# air_quality_monitor.net
KiCad netlist of a schematic drawn in Altium Designer
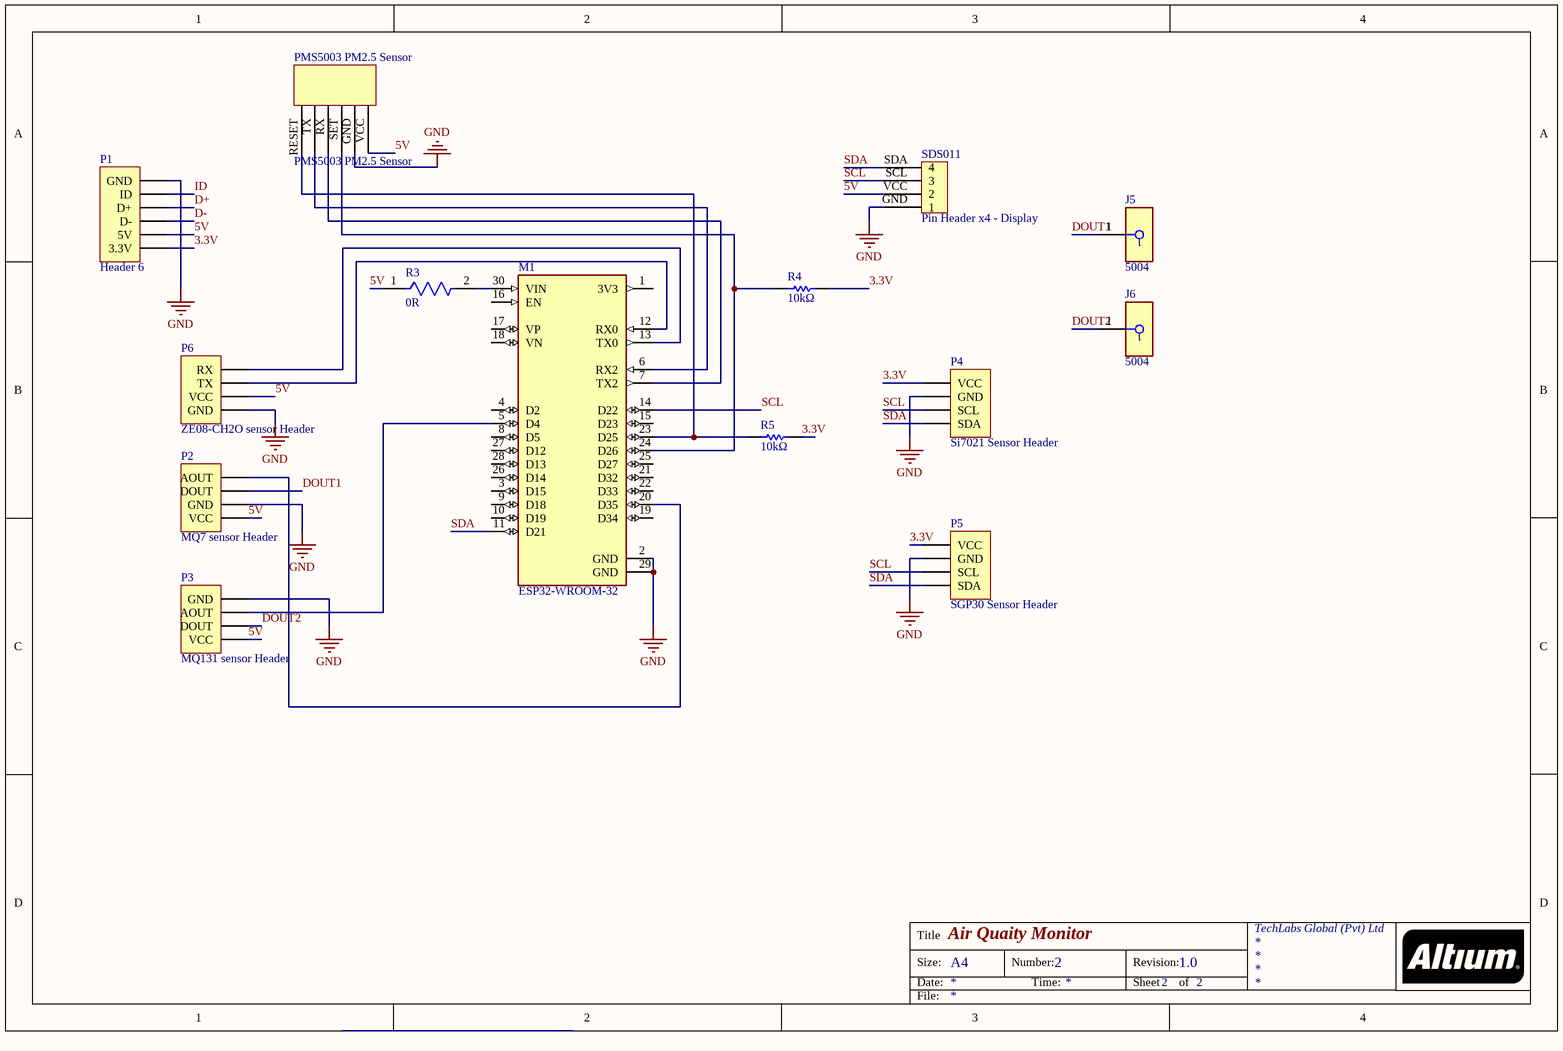
[diagram p0: air quality monitor.SchDoc]

(export (version "E")
  (design (tool "Eeschema 10.0.6"))
  (components
    (comp (ref "J5")
      (value "5004")
      (footprint "FP-5004-MFG")
      (description "PC TEST POINT MINIATURE YELLOW")
      (fields (field (name "MANUFACTURER") "Keystone") (field (name "LCSC PART #") "C2906762"))
      (libsource (lib "Altium Content Vault") (part "98815daf2f2c152b0c43f5ab9800df6"))
    )
    (comp (ref "J6")
      (value "5004")
      (footprint "FP-5004-MFG")
      (description "PC TEST POINT MINIATURE YELLOW")
      (fields (field (name "MANUFACTURER") "Keystone") (field (name "LCSC PART #") "C2906762"))
      (libsource (lib "Altium Content Vault") (part "98815daf2f2c152b0c43f5ab9800df6"))
    )
    (comp (ref "M1")
      (value "ESP32-WROOM-32")
      (footprint "ESP32-DEVKIT-V1")
      (libsource (lib "Modules") (part "ESP32-DEVKIT-V1"))
    )
    (comp (ref "P1")
      (value "Header 6")
      (footprint "HDR1X6")
      (description "Header, 6-Pin")
      (fields (field (name "PUBLISHER") "Altium Limited"))
      (libsource (lib "Miscellaneous Connectors") (part "Header 6"))
    )
    (comp (ref "P2")
      (value "MQ7 sensor Header")
      (footprint "HDR1X4")
      (description "Header, 4-Pin")
      (fields (field (name "PUBLISHER") "Altium Limited"))
      (libsource (lib "") (part "Header 4_2"))
    )
    (comp (ref "P3")
      (value "MQ131 sensor Header")
      (footprint "HDR1X4")
      (description "Header, 4-Pin")
      (fields (field (name "PUBLISHER") "Altium Limited"))
      (libsource (lib "") (part "Header 4_3"))
    )
    (comp (ref "P4")
      (value "Si7021 Sensor Header")
      (footprint "HDR1X4")
      (description "Header, 4-Pin")
      (fields (field (name "PUBLISHER") "Altium Limited"))
      (libsource (lib "") (part "Header 4_1"))
    )
    (comp (ref "P5")
      (value "SGP30 Sensor Header")
      (footprint "HDR1X4")
      (description "Header, 4-Pin")
      (fields (field (name "PUBLISHER") "Altium Limited"))
      (libsource (lib "") (part "Header 4_1"))
    )
    (comp (ref "P6")
      (value "ZE08-CH2O sensor Header")
      (footprint "HDR1X4")
      (description "Header, 4-Pin")
      (fields (field (name "PUBLISHER") "Altium Limited"))
      (libsource (lib "Miscellaneous Connectors") (part "Header 4"))
    )
    (comp (ref "PMS5003 PM2.5 Sensor")
      (value "PMS5003 PM2.5 Sensor")
      (footprint "PMS5003 PM2.5 Sensor")
      (libsource (lib "DIY Air Quality Monitor Library") (part "PMS5003 PM2.5 Sensor"))
    )
    (comp (ref "R3")
      (value "0R")
      (footprint "FP-RC0402-0_4-IPC_A")
      (description "RES SMD 0 OHM JUMPER 1/16W 0402")
      (fields (field (name "MANUFACTURER") "Yageo") (field (name "LCSC PART #") "C106231"))
      (libsource (lib "Altium Content Vault") (part "1029c3af85768c4190bb7ad29bc67b5"))
    )
    (comp (ref "R4")
      (value "10kΩ")
      (footprint "RESC1005X40X25LL05T10")
      (description "62.5mW 50V ±100ppm/℃ ±1% -55℃~+155℃ 10kΩ 0402 Chip Resistor - Surface Mount ROHS")
      (fields (field (name "MFR. PART #") "RC0402FR-0710KL") (field (name "MANUFACTURER") "Yageo / Phycomp"))
      (libsource (lib "Altium Content Vault") (part "RES"))
    )
    (comp (ref "R5")
      (value "10kΩ")
      (footprint "RESC1005X40X25LL05T10")
      (description "62.5mW 50V ±100ppm/℃ ±1% -55℃~+155℃ 10kΩ 0402 Chip Resistor - Surface Mount ROHS")
      (fields (field (name "MFR. PART #") "RC0402FR-0710KL") (field (name "MANUFACTURER") "Yageo / Phycomp"))
      (libsource (lib "Altium Content Vault") (part "RES"))
    )
    (comp (ref "SDS011")
      (value "Pin Header x4 - Display")
      (footprint "dispay")
      (libsource (lib "display") (part "Pin Header x4 - Display"))
    )
  )
  (nets
    (net (code "1") (name "/3.3V") (class "Default")
      (node (ref "P1") (pin "1") (pinfunction "3.3V_1") (pintype "passive"))
      (node (ref "P4") (pin "1") (pinfunction "VCC_1") (pintype "passive"))
      (node (ref "P5") (pin "1") (pinfunction "VCC_1") (pintype "passive"))
      (node (ref "R4") (pin "2") (pinfunction "2_2") (pintype "passive"))
      (node (ref "R5") (pin "2") (pinfunction "2_2") (pintype "passive"))
    )
    (net (code "2") (name "/5V") (class "Default")
      (node (ref "P1") (pin "2") (pinfunction "5V_2") (pintype "passive"))
      (node (ref "P2") (pin "1") (pinfunction "VCC_1") (pintype "passive"))
      (node (ref "P3") (pin "1") (pinfunction "VCC_1") (pintype "passive"))
      (node (ref "P6") (pin "2") (pinfunction "VCC_2") (pintype "passive"))
      (node (ref "PMS5003 PM2.5 Sensor") (pin "VCC") (pintype "passive"))
      (node (ref "R3") (pin "1") (pinfunction "1_1") (pintype "passive"))
      (node (ref "SDS011") (pin "VCC") (pinfunction "2_VCC") (pintype "passive"))
    )
    (net (code "3") (name "/D+") (class "Default")
      (node (ref "P1") (pin "4") (pinfunction "D+_4") (pintype "passive"))
    )
    (net (code "4") (name "/D-") (class "Default")
      (node (ref "P1") (pin "3") (pinfunction "D-_3") (pintype "passive"))
    )
    (net (code "5") (name "/DOUT1") (class "Default")
      (node (ref "J5") (pin "1") (pinfunction "1_1") (pintype "passive"))
      (node (ref "P2") (pin "3") (pinfunction "DOUT_3") (pintype "passive"))
    )
    (net (code "6") (name "/DOUT2") (class "Default")
      (node (ref "J6") (pin "1") (pinfunction "1_1") (pintype "passive"))
      (node (ref "P3") (pin "2") (pinfunction "DOUT_2") (pintype "passive"))
    )
    (net (code "7") (name "/ID") (class "Default")
      (node (ref "P1") (pin "5") (pinfunction "ID_5") (pintype "passive"))
    )
    (net (code "8") (name "/SCL") (class "Default")
      (node (ref "M1") (pin "14") (pinfunction "D22_14") (pintype "bidirectional"))
      (node (ref "P4") (pin "3") (pinfunction "SCL_3") (pintype "passive"))
      (node (ref "P5") (pin "3") (pinfunction "SCL_3") (pintype "passive"))
      (node (ref "SDS011") (pin "SCL") (pinfunction "3_SCL") (pintype "passive"))
    )
    (net (code "9") (name "/SDA") (class "Default")
      (node (ref "M1") (pin "11") (pinfunction "D21_11") (pintype "bidirectional"))
      (node (ref "P4") (pin "4") (pinfunction "SDA_4") (pintype "passive"))
      (node (ref "P5") (pin "4") (pinfunction "SDA_4") (pintype "passive"))
      (node (ref "SDS011") (pin "SDA") (pinfunction "4_SDA") (pintype "passive"))
    )
    (net (code "10") (name "GND") (class "Default")
      (node (ref "M1") (pin "2") (pinfunction "GND_2") (pintype "power_in"))
      (node (ref "M1") (pin "29") (pinfunction "GND_29") (pintype "power_in"))
      (node (ref "P1") (pin "6") (pinfunction "GND_6") (pintype "passive"))
      (node (ref "P2") (pin "2") (pinfunction "GND_2") (pintype "passive"))
      (node (ref "P3") (pin "4") (pinfunction "GND_4") (pintype "passive"))
      (node (ref "P4") (pin "2") (pinfunction "GND_2") (pintype "passive"))
      (node (ref "P5") (pin "2") (pinfunction "GND_2") (pintype "passive"))
      (node (ref "P6") (pin "1") (pinfunction "GND_1") (pintype "passive"))
      (node (ref "PMS5003 PM2.5 Sensor") (pin "GND") (pintype "passive"))
      (node (ref "SDS011") (pin "GND") (pinfunction "1_GND") (pintype "passive"))
    )
    (net (code "11") (name "Net-(M1-D4)") (class "Default")
      (node (ref "M1") (pin "5") (pinfunction "D4_5") (pintype "bidirectional"))
      (node (ref "P3") (pin "3") (pinfunction "AOUT_3") (pintype "passive"))
    )
    (net (code "12") (name "Net-(M1-D25)") (class "Default")
      (node (ref "M1") (pin "23") (pinfunction "D25_23") (pintype "bidirectional"))
      (node (ref "PMS5003 PM2.5 Sensor") (pin "RESET") (pintype "passive"))
      (node (ref "R5") (pin "1") (pinfunction "1_1") (pintype "passive"))
    )
    (net (code "13") (name "Net-(M1-D26)") (class "Default")
      (node (ref "M1") (pin "24") (pinfunction "D26_24") (pintype "bidirectional"))
      (node (ref "PMS5003 PM2.5 Sensor") (pin "SET") (pintype "passive"))
      (node (ref "R4") (pin "1") (pinfunction "1_1") (pintype "passive"))
    )
    (net (code "14") (name "Net-(M1-D35)") (class "Default")
      (node (ref "M1") (pin "20") (pinfunction "D35_20") (pintype "bidirectional"))
      (node (ref "P2") (pin "4") (pinfunction "AOUT_4") (pintype "passive"))
    )
    (net (code "15") (name "Net-(M1-RX0)") (class "Default")
      (node (ref "M1") (pin "12") (pinfunction "RX0_12") (pintype "input"))
      (node (ref "P6") (pin "3") (pinfunction "TX_3") (pintype "passive"))
    )
    (net (code "16") (name "Net-(M1-RX2)") (class "Default")
      (node (ref "M1") (pin "6") (pinfunction "RX2_6") (pintype "input"))
      (node (ref "PMS5003 PM2.5 Sensor") (pin "TX") (pintype "passive"))
    )
    (net (code "17") (name "Net-(M1-TX0)") (class "Default")
      (node (ref "M1") (pin "13") (pinfunction "TX0_13") (pintype "output"))
      (node (ref "P6") (pin "4") (pinfunction "RX_4") (pintype "passive"))
    )
    (net (code "18") (name "Net-(M1-TX2)") (class "Default")
      (node (ref "M1") (pin "7") (pinfunction "TX2_7") (pintype "output"))
      (node (ref "PMS5003 PM2.5 Sensor") (pin "RX") (pintype "passive"))
    )
    (net (code "19") (name "Net-(M1-VIN)") (class "Default")
      (node (ref "M1") (pin "30") (pinfunction "VIN_30") (pintype "input"))
      (node (ref "R3") (pin "2") (pinfunction "2_2") (pintype "passive"))
    )
    (net (code "20") (name "unconnected-(M1-3V3-Pad1)") (class "Default")
      (node (ref "M1") (pin "1") (pinfunction "3V3_1") (pintype "output"))
    )
    (net (code "21") (name "unconnected-(M1-D2-Pad4)") (class "Default")
      (node (ref "M1") (pin "4") (pinfunction "D2_4") (pintype "bidirectional"))
    )
    (net (code "22") (name "unconnected-(M1-D5-Pad8)") (class "Default")
      (node (ref "M1") (pin "8") (pinfunction "D5_8") (pintype "bidirectional"))
    )
    (net (code "23") (name "unconnected-(M1-D12-Pad27)") (class "Default")
      (node (ref "M1") (pin "27") (pinfunction "D12_27") (pintype "bidirectional"))
    )
    (net (code "24") (name "unconnected-(M1-D13-Pad28)") (class "Default")
      (node (ref "M1") (pin "28") (pinfunction "D13_28") (pintype "bidirectional"))
    )
    (net (code "25") (name "unconnected-(M1-D14-Pad26)") (class "Default")
      (node (ref "M1") (pin "26") (pinfunction "D14_26") (pintype "bidirectional"))
    )
    (net (code "26") (name "unconnected-(M1-D15-Pad3)") (class "Default")
      (node (ref "M1") (pin "3") (pinfunction "D15_3") (pintype "bidirectional"))
    )
    (net (code "27") (name "unconnected-(M1-D18-Pad9)") (class "Default")
      (node (ref "M1") (pin "9") (pinfunction "D18_9") (pintype "bidirectional"))
    )
    (net (code "28") (name "unconnected-(M1-D19-Pad10)") (class "Default")
      (node (ref "M1") (pin "10") (pinfunction "D19_10") (pintype "bidirectional"))
    )
    (net (code "29") (name "unconnected-(M1-D23-Pad15)") (class "Default")
      (node (ref "M1") (pin "15") (pinfunction "D23_15") (pintype "bidirectional"))
    )
    (net (code "30") (name "unconnected-(M1-D27-Pad25)") (class "Default")
      (node (ref "M1") (pin "25") (pinfunction "D27_25") (pintype "bidirectional"))
    )
    (net (code "31") (name "unconnected-(M1-D32-Pad21)") (class "Default")
      (node (ref "M1") (pin "21") (pinfunction "D32_21") (pintype "bidirectional"))
    )
    (net (code "32") (name "unconnected-(M1-D33-Pad22)") (class "Default")
      (node (ref "M1") (pin "22") (pinfunction "D33_22") (pintype "bidirectional"))
    )
    (net (code "33") (name "unconnected-(M1-D34-Pad19)") (class "Default")
      (node (ref "M1") (pin "19") (pinfunction "D34_19") (pintype "bidirectional"))
    )
    (net (code "34") (name "unconnected-(M1-EN-Pad16)") (class "Default")
      (node (ref "M1") (pin "16") (pinfunction "EN_16") (pintype "input"))
    )
    (net (code "35") (name "unconnected-(M1-VN-Pad18)") (class "Default")
      (node (ref "M1") (pin "18") (pinfunction "VN_18") (pintype "bidirectional"))
    )
    (net (code "36") (name "unconnected-(M1-VP-Pad17)") (class "Default")
      (node (ref "M1") (pin "17") (pinfunction "VP_17") (pintype "bidirectional"))
    )
  )
)
